# Scratch_Register_16B.net
KiCad netlist of a schematic drawn in Altium Designer
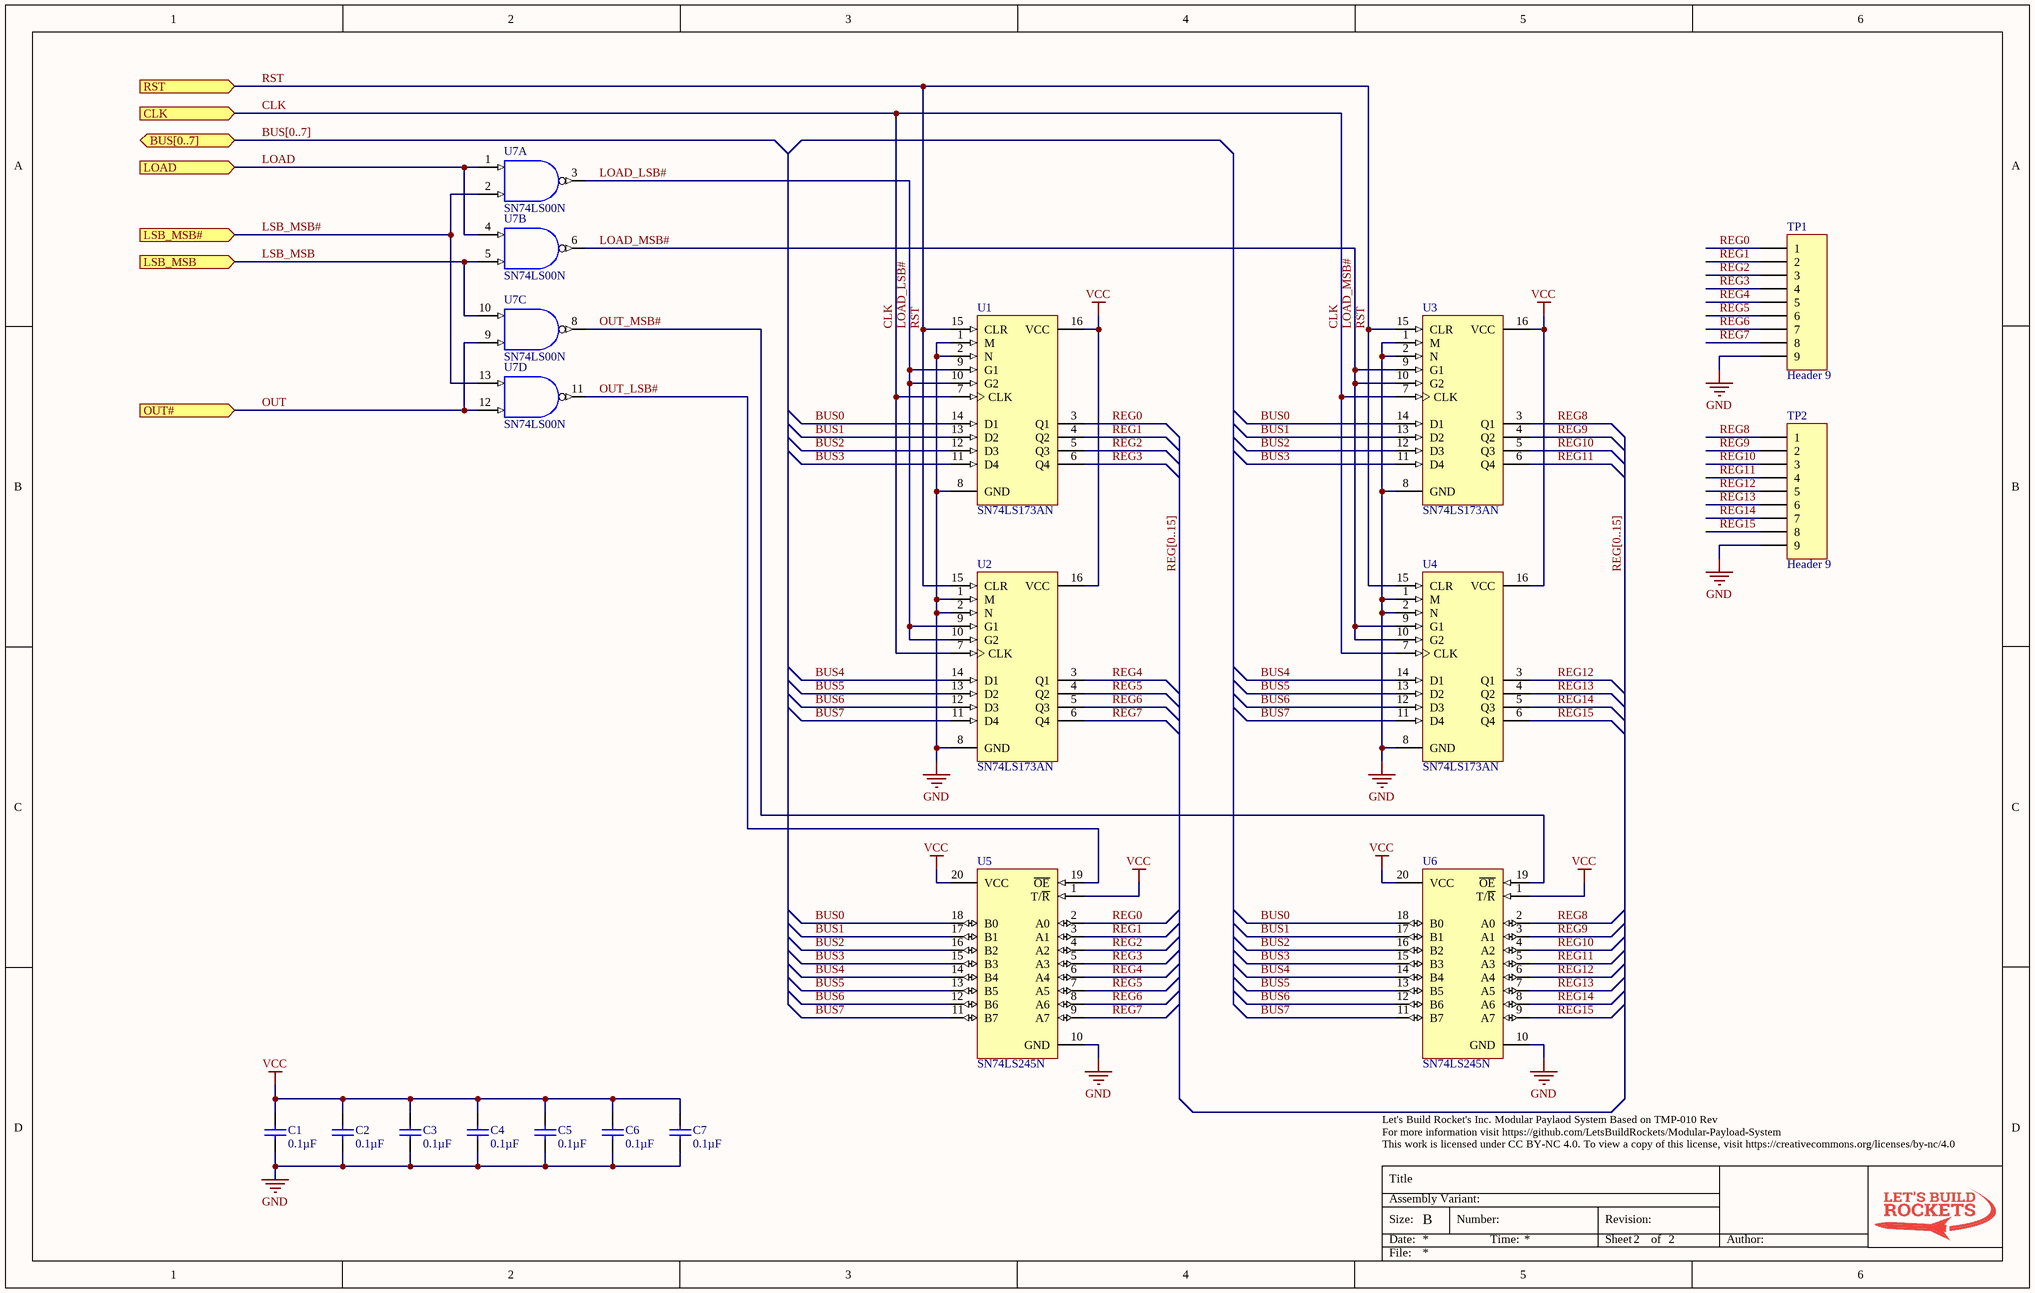
[diagram p0: Scratch_Register_16B.SchDoc]

(export (version "E")
  (design (tool "Eeschema 10.0.6"))
  (components
    (comp (ref "C1")
      (value "K104K15X7RF5TL2")
      (footprint "VISH-K104K15X7RF5TL2")
      (description "Ceramic Capacitor, 100 nF, +/- 10%, 50 V, -55 to 125 degC, 2-Pin THD, RoHS, Tape and Reel")
      (fields
        (field (name "MANUFACTURER") "Vishay")
        (field (name "TOLERANCE") "±10%")
        (field (name "CAPACITANCE") "0.1µF")
      )
      (libsource (lib "Altium Content Vault") (part "CAP-NP-2"))
    )
    (comp (ref "C2")
      (value "K104K15X7RF5TL2")
      (footprint "VISH-K104K15X7RF5TL2")
      (description "Ceramic Capacitor, 100 nF, +/- 10%, 50 V, -55 to 125 degC, 2-Pin THD, RoHS, Tape and Reel")
      (fields
        (field (name "MANUFACTURER") "Vishay")
        (field (name "TOLERANCE") "±10%")
        (field (name "CAPACITANCE") "0.1µF")
      )
      (libsource (lib "Altium Content Vault") (part "CAP-NP-2"))
    )
    (comp (ref "C3")
      (value "K104K15X7RF5TL2")
      (footprint "VISH-K104K15X7RF5TL2")
      (description "Ceramic Capacitor, 100 nF, +/- 10%, 50 V, -55 to 125 degC, 2-Pin THD, RoHS, Tape and Reel")
      (fields
        (field (name "MANUFACTURER") "Vishay")
        (field (name "TOLERANCE") "±10%")
        (field (name "CAPACITANCE") "0.1µF")
      )
      (libsource (lib "Altium Content Vault") (part "CAP-NP-2"))
    )
    (comp (ref "C4")
      (value "K104K15X7RF5TL2")
      (footprint "VISH-K104K15X7RF5TL2")
      (description "Ceramic Capacitor, 100 nF, +/- 10%, 50 V, -55 to 125 degC, 2-Pin THD, RoHS, Tape and Reel")
      (fields
        (field (name "MANUFACTURER") "Vishay")
        (field (name "TOLERANCE") "±10%")
        (field (name "CAPACITANCE") "0.1µF")
      )
      (libsource (lib "Altium Content Vault") (part "CAP-NP-2"))
    )
    (comp (ref "C5")
      (value "K104K15X7RF5TL2")
      (footprint "VISH-K104K15X7RF5TL2")
      (description "Ceramic Capacitor, 100 nF, +/- 10%, 50 V, -55 to 125 degC, 2-Pin THD, RoHS, Tape and Reel")
      (fields
        (field (name "MANUFACTURER") "Vishay")
        (field (name "TOLERANCE") "±10%")
        (field (name "CAPACITANCE") "0.1µF")
      )
      (libsource (lib "Altium Content Vault") (part "CAP-NP-2"))
    )
    (comp (ref "C6")
      (value "K104K15X7RF5TL2")
      (footprint "VISH-K104K15X7RF5TL2")
      (description "Ceramic Capacitor, 100 nF, +/- 10%, 50 V, -55 to 125 degC, 2-Pin THD, RoHS, Tape and Reel")
      (fields
        (field (name "MANUFACTURER") "Vishay")
        (field (name "TOLERANCE") "±10%")
        (field (name "CAPACITANCE") "0.1µF")
      )
      (libsource (lib "Altium Content Vault") (part "CAP-NP-2"))
    )
    (comp (ref "C7")
      (value "K104K15X7RF5TL2")
      (footprint "VISH-K104K15X7RF5TL2")
      (description "Ceramic Capacitor, 100 nF, +/- 10%, 50 V, -55 to 125 degC, 2-Pin THD, RoHS, Tape and Reel")
      (fields
        (field (name "MANUFACTURER") "Vishay")
        (field (name "TOLERANCE") "±10%")
        (field (name "CAPACITANCE") "0.1µF")
      )
      (libsource (lib "Altium Content Vault") (part "CAP-NP-2"))
    )
    (comp (ref "TP1")
      (value "Header 9")
      (footprint "HDR1X9")
      (description "Header, 9-Pin")
      (fields (field (name "PUBLISHER") "Altium Limited"))
      (libsource (lib "Miscellaneous Connectors") (part "Header 9"))
    )
    (comp (ref "TP2")
      (value "Header 9")
      (footprint "HDR1X9")
      (description "Header, 9-Pin")
      (fields (field (name "PUBLISHER") "Altium Limited"))
      (libsource (lib "Miscellaneous Connectors") (part "Header 9"))
    )
    (comp (ref "U1")
      (value "SN74LS173AN")
      (footprint "N016D")
      (description "4-Bit D-Type Register with 3-State Outputs")
      (fields (field (name "PUBLISHER") "Altium Limited"))
      (libsource (lib "TI Logic Flip-Flop") (part "SN74LS173AN"))
    )
    (comp (ref "U2")
      (value "SN74LS173AN")
      (footprint "N016D")
      (description "4-Bit D-Type Register with 3-State Outputs")
      (fields (field (name "PUBLISHER") "Altium Limited"))
      (libsource (lib "TI Logic Flip-Flop") (part "SN74LS173AN"))
    )
    (comp (ref "U3")
      (value "SN74LS173AN")
      (footprint "N016D")
      (description "4-Bit D-Type Register with 3-State Outputs")
      (fields (field (name "PUBLISHER") "Altium Limited"))
      (libsource (lib "TI Logic Flip-Flop") (part "SN74LS173AN"))
    )
    (comp (ref "U4")
      (value "SN74LS173AN")
      (footprint "N016D")
      (description "4-Bit D-Type Register with 3-State Outputs")
      (fields (field (name "PUBLISHER") "Altium Limited"))
      (libsource (lib "TI Logic Flip-Flop") (part "SN74LS173AN"))
    )
    (comp (ref "U5")
      (value "SN74LS245N")
      (footprint "N020")
      (description "Octal Bus Transceiver with 3-State Outputs")
      (fields (field (name "PUBLISHER") "Altium Limited"))
      (libsource (lib "TI Interface 8-Bit Line Transceiver") (part "SN74LS245N"))
    )
    (comp (ref "U6")
      (value "SN74LS245N")
      (footprint "N020")
      (description "Octal Bus Transceiver with 3-State Outputs")
      (fields (field (name "PUBLISHER") "Altium Limited"))
      (libsource (lib "TI Interface 8-Bit Line Transceiver") (part "SN74LS245N"))
    )
    (comp (ref "U7")
      (value "SN74LS00N")
      (footprint "N014")
      (description "Quadruple 2-Input Positive-NAND Gate")
      (fields (field (name "PUBLISHER") "Altium Limited"))
      (libsource (lib "TI Logic Gate 2") (part "SN74LS00N"))
    )
  )
  (nets
    (net (code "1") (name "/BUS0") (class "Default")
      (node (ref "U1") (pin "14") (pinfunction "D1_14") (pintype "input"))
      (node (ref "U3") (pin "14") (pinfunction "D1_14") (pintype "input"))
      (node (ref "U5") (pin "18") (pinfunction "B0_18") (pintype "bidirectional"))
      (node (ref "U6") (pin "18") (pinfunction "B0_18") (pintype "bidirectional"))
    )
    (net (code "2") (name "/BUS1") (class "Default")
      (node (ref "U1") (pin "13") (pinfunction "D2_13") (pintype "input"))
      (node (ref "U3") (pin "13") (pinfunction "D2_13") (pintype "input"))
      (node (ref "U5") (pin "17") (pinfunction "B1_17") (pintype "bidirectional"))
      (node (ref "U6") (pin "17") (pinfunction "B1_17") (pintype "bidirectional"))
    )
    (net (code "3") (name "/BUS2") (class "Default")
      (node (ref "U1") (pin "12") (pinfunction "D3_12") (pintype "input"))
      (node (ref "U3") (pin "12") (pinfunction "D3_12") (pintype "input"))
      (node (ref "U5") (pin "16") (pinfunction "B2_16") (pintype "bidirectional"))
      (node (ref "U6") (pin "16") (pinfunction "B2_16") (pintype "bidirectional"))
    )
    (net (code "4") (name "/BUS3") (class "Default")
      (node (ref "U1") (pin "11") (pinfunction "D4_11") (pintype "input"))
      (node (ref "U3") (pin "11") (pinfunction "D4_11") (pintype "input"))
      (node (ref "U5") (pin "15") (pinfunction "B3_15") (pintype "bidirectional"))
      (node (ref "U6") (pin "15") (pinfunction "B3_15") (pintype "bidirectional"))
    )
    (net (code "5") (name "/BUS4") (class "Default")
      (node (ref "U2") (pin "14") (pinfunction "D1_14") (pintype "input"))
      (node (ref "U4") (pin "14") (pinfunction "D1_14") (pintype "input"))
      (node (ref "U5") (pin "14") (pinfunction "B4_14") (pintype "bidirectional"))
      (node (ref "U6") (pin "14") (pinfunction "B4_14") (pintype "bidirectional"))
    )
    (net (code "6") (name "/BUS5") (class "Default")
      (node (ref "U2") (pin "13") (pinfunction "D2_13") (pintype "input"))
      (node (ref "U4") (pin "13") (pinfunction "D2_13") (pintype "input"))
      (node (ref "U5") (pin "13") (pinfunction "B5_13") (pintype "bidirectional"))
      (node (ref "U6") (pin "13") (pinfunction "B5_13") (pintype "bidirectional"))
    )
    (net (code "7") (name "/BUS6") (class "Default")
      (node (ref "U2") (pin "12") (pinfunction "D3_12") (pintype "input"))
      (node (ref "U4") (pin "12") (pinfunction "D3_12") (pintype "input"))
      (node (ref "U5") (pin "12") (pinfunction "B6_12") (pintype "bidirectional"))
      (node (ref "U6") (pin "12") (pinfunction "B6_12") (pintype "bidirectional"))
    )
    (net (code "8") (name "/BUS7") (class "Default")
      (node (ref "U2") (pin "11") (pinfunction "D4_11") (pintype "input"))
      (node (ref "U4") (pin "11") (pinfunction "D4_11") (pintype "input"))
      (node (ref "U5") (pin "11") (pinfunction "B7_11") (pintype "bidirectional"))
      (node (ref "U6") (pin "11") (pinfunction "B7_11") (pintype "bidirectional"))
    )
    (net (code "10") (name "/CLK") (class "Default")
      (node (ref "U1") (pin "7") (pinfunction "CLK_7") (pintype "input"))
      (node (ref "U2") (pin "7") (pinfunction "CLK_7") (pintype "input"))
      (node (ref "U3") (pin "7") (pinfunction "CLK_7") (pintype "input"))
      (node (ref "U4") (pin "7") (pinfunction "CLK_7") (pintype "input"))
    )
    (net (code "11") (name "/LOAD") (class "Default")
      (node (ref "U7") (pin "1") (pinfunction "A_1") (pintype "input"))
      (node (ref "U7") (pin "4") (pinfunction "A_4") (pintype "input"))
    )
    (net (code "12") (name "/LOAD_LSB#") (class "Default")
      (node (ref "U1") (pin "10") (pinfunction "G2_10") (pintype "input"))
      (node (ref "U1") (pin "9") (pinfunction "G1_9") (pintype "input"))
      (node (ref "U2") (pin "10") (pinfunction "G2_10") (pintype "input"))
      (node (ref "U2") (pin "9") (pinfunction "G1_9") (pintype "input"))
      (node (ref "U7") (pin "3") (pinfunction "Y_3") (pintype "output"))
    )
    (net (code "13") (name "/LOAD_MSB#") (class "Default")
      (node (ref "U3") (pin "10") (pinfunction "G2_10") (pintype "input"))
      (node (ref "U3") (pin "9") (pinfunction "G1_9") (pintype "input"))
      (node (ref "U4") (pin "10") (pinfunction "G2_10") (pintype "input"))
      (node (ref "U4") (pin "9") (pinfunction "G1_9") (pintype "input"))
      (node (ref "U7") (pin "6") (pinfunction "Y_6") (pintype "output"))
    )
    (net (code "14") (name "/LSB_MSB") (class "Default")
      (node (ref "U7") (pin "10") (pinfunction "B_10") (pintype "input"))
      (node (ref "U7") (pin "5") (pinfunction "B_5") (pintype "input"))
    )
    (net (code "15") (name "/LSB_MSB#") (class "Default")
      (node (ref "U7") (pin "13") (pinfunction "B_13") (pintype "input"))
      (node (ref "U7") (pin "2") (pinfunction "B_2") (pintype "input"))
    )
    (net (code "16") (name "/OUT") (class "Default")
      (node (ref "U7") (pin "12") (pinfunction "A_12") (pintype "input"))
      (node (ref "U7") (pin "9") (pinfunction "A_9") (pintype "input"))
    )
    (net (code "17") (name "/OUT_LSB#") (class "Default")
      (node (ref "U5") (pin "19") (pinfunction "~{OE}_19") (pintype "input"))
      (node (ref "U7") (pin "11") (pinfunction "Y_11") (pintype "output"))
    )
    (net (code "18") (name "/OUT_MSB#") (class "Default")
      (node (ref "U6") (pin "19") (pinfunction "~{OE}_19") (pintype "input"))
      (node (ref "U7") (pin "8") (pinfunction "Y_8") (pintype "output"))
    )
    (net (code "19") (name "/REG0") (class "Default")
      (node (ref "TP1") (pin "1") (pinfunction "1_1") (pintype "passive"))
      (node (ref "U1") (pin "3") (pinfunction "Q1_3") (pintype "tri_state"))
      (node (ref "U5") (pin "2") (pinfunction "A0_2") (pintype "bidirectional"))
    )
    (net (code "20") (name "/REG1") (class "Default")
      (node (ref "TP1") (pin "2") (pinfunction "2_2") (pintype "passive"))
      (node (ref "U1") (pin "4") (pinfunction "Q2_4") (pintype "tri_state"))
      (node (ref "U5") (pin "3") (pinfunction "A1_3") (pintype "bidirectional"))
    )
    (net (code "21") (name "/REG2") (class "Default")
      (node (ref "TP1") (pin "3") (pinfunction "3_3") (pintype "passive"))
      (node (ref "U1") (pin "5") (pinfunction "Q3_5") (pintype "tri_state"))
      (node (ref "U5") (pin "4") (pinfunction "A2_4") (pintype "bidirectional"))
    )
    (net (code "22") (name "/REG3") (class "Default")
      (node (ref "TP1") (pin "4") (pinfunction "4_4") (pintype "passive"))
      (node (ref "U1") (pin "6") (pinfunction "Q4_6") (pintype "tri_state"))
      (node (ref "U5") (pin "5") (pinfunction "A3_5") (pintype "bidirectional"))
    )
    (net (code "23") (name "/REG4") (class "Default")
      (node (ref "TP1") (pin "5") (pinfunction "5_5") (pintype "passive"))
      (node (ref "U2") (pin "3") (pinfunction "Q1_3") (pintype "tri_state"))
      (node (ref "U5") (pin "6") (pinfunction "A4_6") (pintype "bidirectional"))
    )
    (net (code "24") (name "/REG5") (class "Default")
      (node (ref "TP1") (pin "6") (pinfunction "6_6") (pintype "passive"))
      (node (ref "U2") (pin "4") (pinfunction "Q2_4") (pintype "tri_state"))
      (node (ref "U5") (pin "7") (pinfunction "A5_7") (pintype "bidirectional"))
    )
    (net (code "25") (name "/REG6") (class "Default")
      (node (ref "TP1") (pin "7") (pinfunction "7_7") (pintype "passive"))
      (node (ref "U2") (pin "5") (pinfunction "Q3_5") (pintype "tri_state"))
      (node (ref "U5") (pin "8") (pinfunction "A6_8") (pintype "bidirectional"))
    )
    (net (code "26") (name "/REG7") (class "Default")
      (node (ref "TP1") (pin "8") (pinfunction "8_8") (pintype "passive"))
      (node (ref "U2") (pin "6") (pinfunction "Q4_6") (pintype "tri_state"))
      (node (ref "U5") (pin "9") (pinfunction "A7_9") (pintype "bidirectional"))
    )
    (net (code "27") (name "/REG8") (class "Default")
      (node (ref "TP2") (pin "1") (pinfunction "1_1") (pintype "passive"))
      (node (ref "U3") (pin "3") (pinfunction "Q1_3") (pintype "tri_state"))
      (node (ref "U6") (pin "2") (pinfunction "A0_2") (pintype "bidirectional"))
    )
    (net (code "28") (name "/REG9") (class "Default")
      (node (ref "TP2") (pin "2") (pinfunction "2_2") (pintype "passive"))
      (node (ref "U3") (pin "4") (pinfunction "Q2_4") (pintype "tri_state"))
      (node (ref "U6") (pin "3") (pinfunction "A1_3") (pintype "bidirectional"))
    )
    (net (code "29") (name "/REG10") (class "Default")
      (node (ref "TP2") (pin "3") (pinfunction "3_3") (pintype "passive"))
      (node (ref "U3") (pin "5") (pinfunction "Q3_5") (pintype "tri_state"))
      (node (ref "U6") (pin "4") (pinfunction "A2_4") (pintype "bidirectional"))
    )
    (net (code "30") (name "/REG11") (class "Default")
      (node (ref "TP2") (pin "4") (pinfunction "4_4") (pintype "passive"))
      (node (ref "U3") (pin "6") (pinfunction "Q4_6") (pintype "tri_state"))
      (node (ref "U6") (pin "5") (pinfunction "A3_5") (pintype "bidirectional"))
    )
    (net (code "31") (name "/REG12") (class "Default")
      (node (ref "TP2") (pin "5") (pinfunction "5_5") (pintype "passive"))
      (node (ref "U4") (pin "3") (pinfunction "Q1_3") (pintype "tri_state"))
      (node (ref "U6") (pin "6") (pinfunction "A4_6") (pintype "bidirectional"))
    )
    (net (code "32") (name "/REG13") (class "Default")
      (node (ref "TP2") (pin "6") (pinfunction "6_6") (pintype "passive"))
      (node (ref "U4") (pin "4") (pinfunction "Q2_4") (pintype "tri_state"))
      (node (ref "U6") (pin "7") (pinfunction "A5_7") (pintype "bidirectional"))
    )
    (net (code "33") (name "/REG14") (class "Default")
      (node (ref "TP2") (pin "7") (pinfunction "7_7") (pintype "passive"))
      (node (ref "U4") (pin "5") (pinfunction "Q3_5") (pintype "tri_state"))
      (node (ref "U6") (pin "8") (pinfunction "A6_8") (pintype "bidirectional"))
    )
    (net (code "34") (name "/REG15") (class "Default")
      (node (ref "TP2") (pin "8") (pinfunction "8_8") (pintype "passive"))
      (node (ref "U4") (pin "6") (pinfunction "Q4_6") (pintype "tri_state"))
      (node (ref "U6") (pin "9") (pinfunction "A7_9") (pintype "bidirectional"))
    )
    (net (code "36") (name "/RST") (class "Default")
      (node (ref "U1") (pin "15") (pinfunction "CLR_15") (pintype "input"))
      (node (ref "U2") (pin "15") (pinfunction "CLR_15") (pintype "input"))
      (node (ref "U3") (pin "15") (pinfunction "CLR_15") (pintype "input"))
      (node (ref "U4") (pin "15") (pinfunction "CLR_15") (pintype "input"))
    )
    (net (code "37") (name "GND") (class "Default")
      (node (ref "C1") (pin "2") (pinfunction "2_2") (pintype "passive"))
      (node (ref "C2") (pin "2") (pinfunction "2_2") (pintype "passive"))
      (node (ref "C3") (pin "2") (pinfunction "2_2") (pintype "passive"))
      (node (ref "C4") (pin "2") (pinfunction "2_2") (pintype "passive"))
      (node (ref "C5") (pin "2") (pinfunction "2_2") (pintype "passive"))
      (node (ref "C6") (pin "2") (pinfunction "2_2") (pintype "passive"))
      (node (ref "C7") (pin "2") (pinfunction "2_2") (pintype "passive"))
      (node (ref "TP1") (pin "9") (pinfunction "9_9") (pintype "passive"))
      (node (ref "TP2") (pin "9") (pinfunction "9_9") (pintype "passive"))
      (node (ref "U1") (pin "1") (pinfunction "M_1") (pintype "input"))
      (node (ref "U1") (pin "2") (pinfunction "N_2") (pintype "input"))
      (node (ref "U1") (pin "8") (pinfunction "GND_8") (pintype "power_in"))
      (node (ref "U2") (pin "1") (pinfunction "M_1") (pintype "input"))
      (node (ref "U2") (pin "2") (pinfunction "N_2") (pintype "input"))
      (node (ref "U2") (pin "8") (pinfunction "GND_8") (pintype "power_in"))
      (node (ref "U3") (pin "1") (pinfunction "M_1") (pintype "input"))
      (node (ref "U3") (pin "2") (pinfunction "N_2") (pintype "input"))
      (node (ref "U3") (pin "8") (pinfunction "GND_8") (pintype "power_in"))
      (node (ref "U4") (pin "1") (pinfunction "M_1") (pintype "input"))
      (node (ref "U4") (pin "2") (pinfunction "N_2") (pintype "input"))
      (node (ref "U4") (pin "8") (pinfunction "GND_8") (pintype "power_in"))
      (node (ref "U5") (pin "10") (pinfunction "GND_10") (pintype "power_in"))
      (node (ref "U6") (pin "10") (pinfunction "GND_10") (pintype "power_in"))
      (node (ref "U7") (pin "7") (pinfunction "GND_7") (pintype "power_in"))
    )
    (net (code "38") (name "VCC") (class "Default")
      (node (ref "C1") (pin "1") (pinfunction "1_1") (pintype "passive"))
      (node (ref "C2") (pin "1") (pinfunction "1_1") (pintype "passive"))
      (node (ref "C3") (pin "1") (pinfunction "1_1") (pintype "passive"))
      (node (ref "C4") (pin "1") (pinfunction "1_1") (pintype "passive"))
      (node (ref "C5") (pin "1") (pinfunction "1_1") (pintype "passive"))
      (node (ref "C6") (pin "1") (pinfunction "1_1") (pintype "passive"))
      (node (ref "C7") (pin "1") (pinfunction "1_1") (pintype "passive"))
      (node (ref "U1") (pin "16") (pinfunction "VCC_16") (pintype "power_in"))
      (node (ref "U2") (pin "16") (pinfunction "VCC_16") (pintype "power_in"))
      (node (ref "U3") (pin "16") (pinfunction "VCC_16") (pintype "power_in"))
      (node (ref "U4") (pin "16") (pinfunction "VCC_16") (pintype "power_in"))
      (node (ref "U5") (pin "1") (pinfunction "T/~{R}_1") (pintype "input"))
      (node (ref "U5") (pin "20") (pinfunction "VCC_20") (pintype "power_in"))
      (node (ref "U6") (pin "1") (pinfunction "T/~{R}_1") (pintype "input"))
      (node (ref "U6") (pin "20") (pinfunction "VCC_20") (pintype "power_in"))
      (node (ref "U7") (pin "14") (pinfunction "VCC_14") (pintype "power_in"))
    )
  )
)
